# ANALOG_INPUT_CTRL.net
KiCad netlist of a schematic drawn in Altium Designer
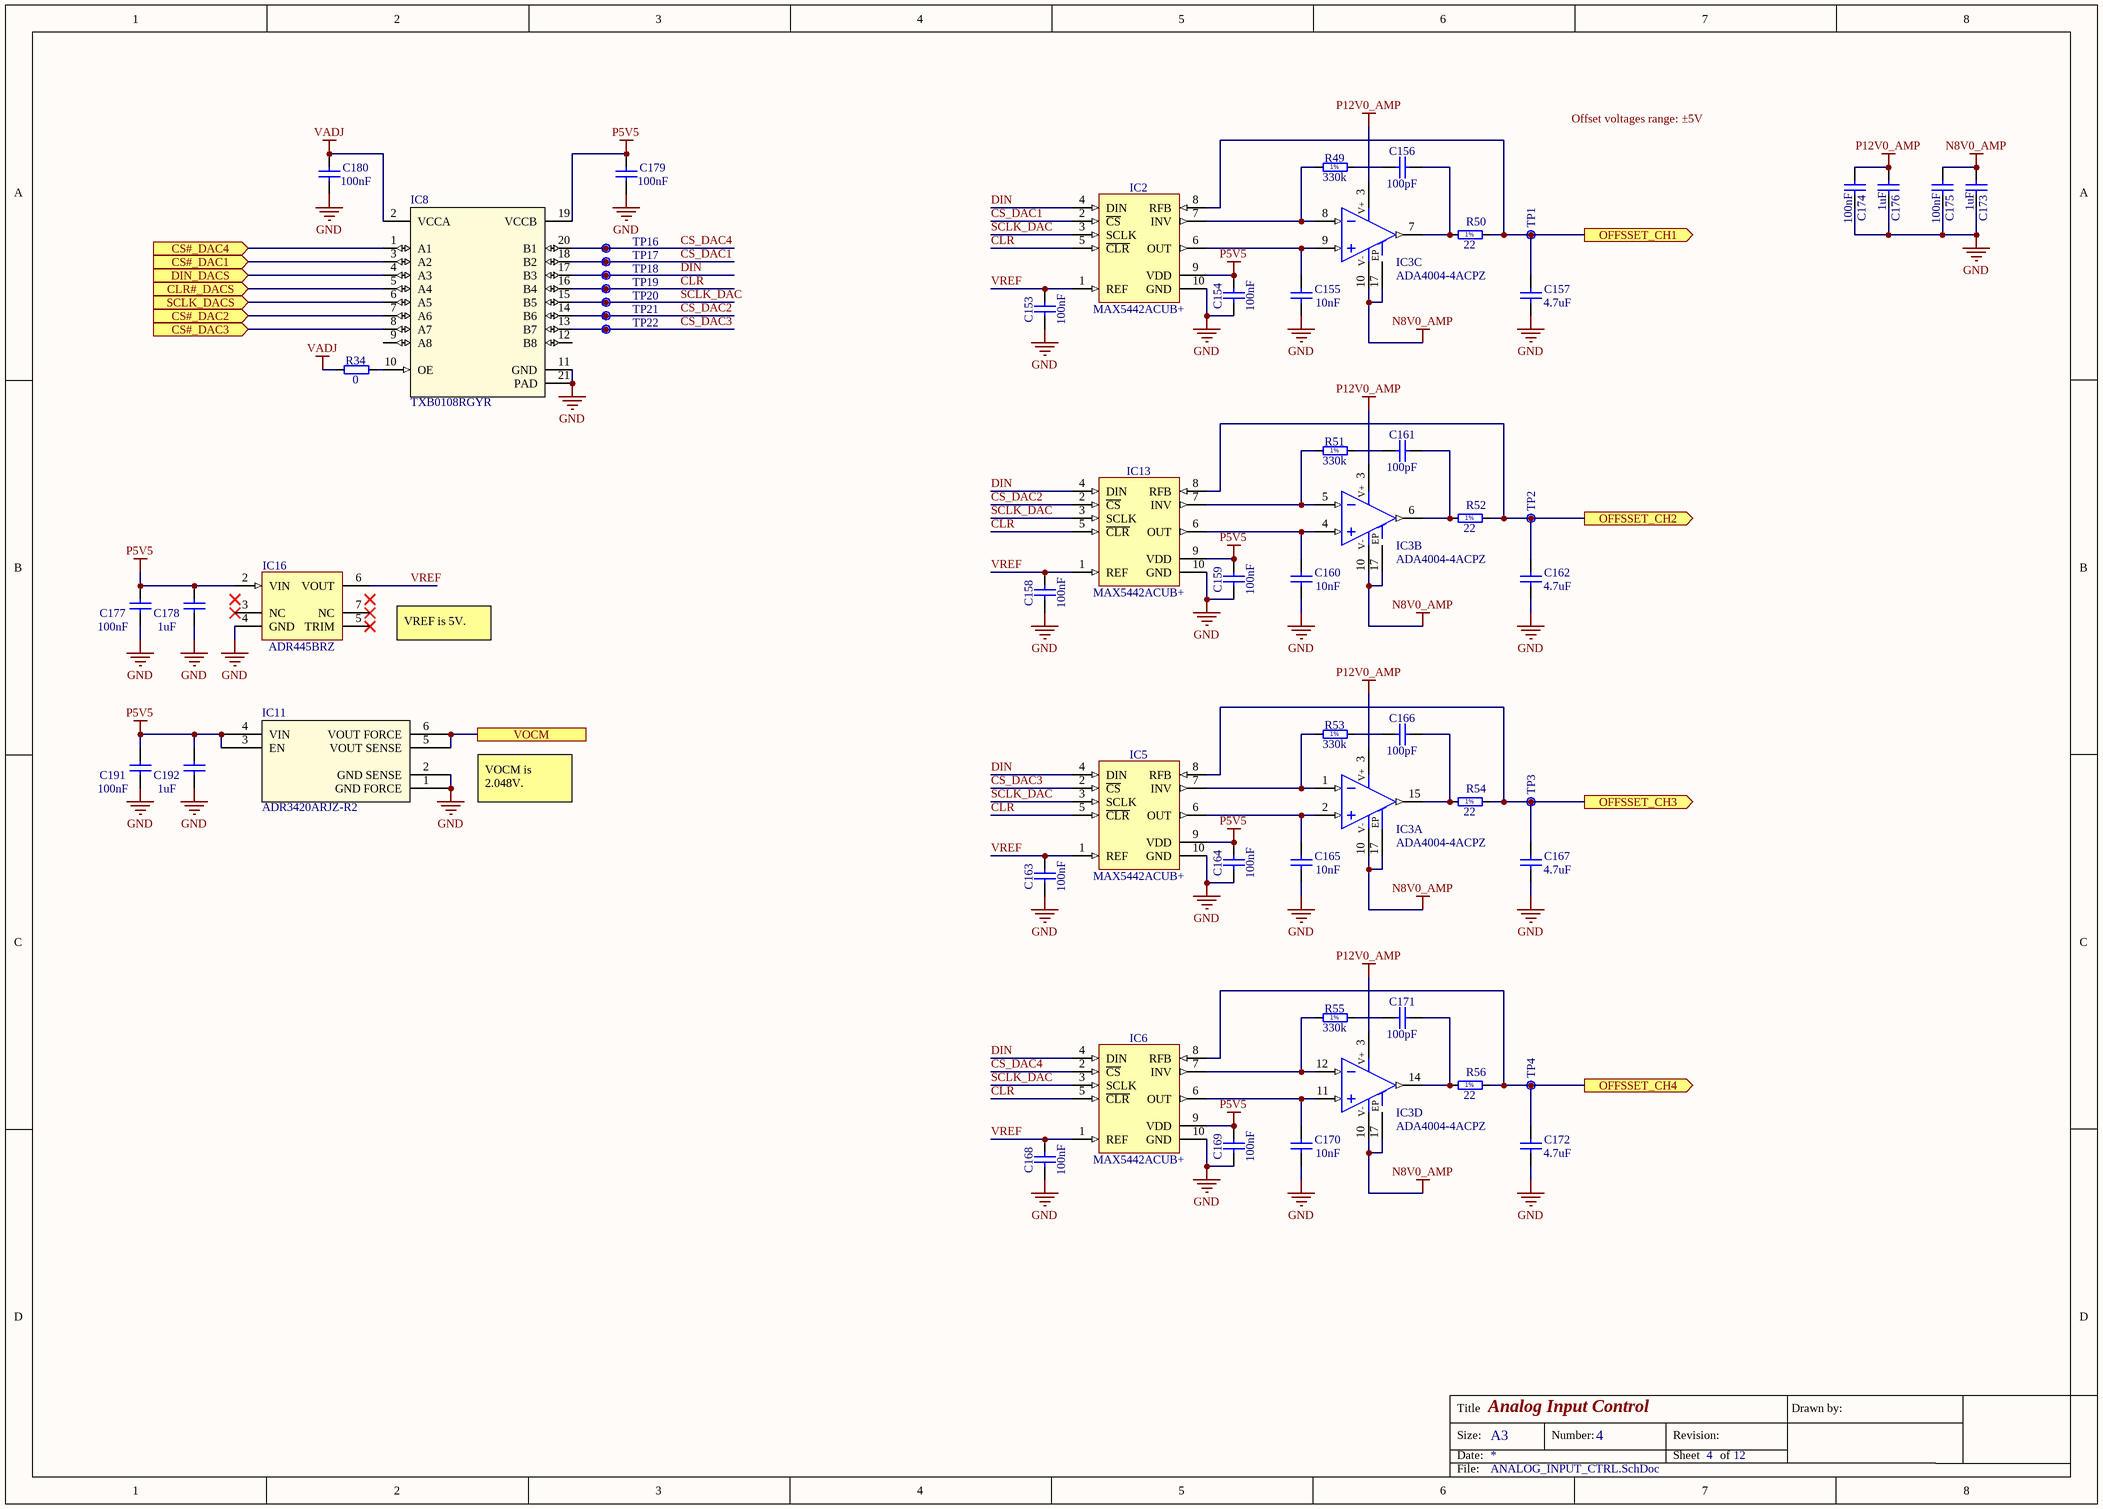
[diagram p0: ANALOG_INPUT_CTRL.SchDoc]

(export (version "E")
  (design (tool "Eeschema 10.0.6"))
  (components
    (comp (ref "C153")
      (value "100nF")
      (footprint "CAPC1005X55N")
      (description "Non-polarised capacitor")
      (fields
        (field (name "PART NUMBER") "CC0402_100NF_16V_10%_X7R")
        (field (name "VOLTAGE") "16V")
        (field (name "AUTHOR") "CERN DEM JLC")
      )
      (libsource (lib "Capacitors") (part "Capacitor - non polarized"))
    )
    (comp (ref "C154")
      (value "100nF")
      (footprint "CAPC1005X55N")
      (description "Non-polarised capacitor")
      (fields
        (field (name "PART NUMBER") "CC0402_100NF_16V_10%_X7R")
        (field (name "VOLTAGE") "16V")
        (field (name "AUTHOR") "CERN DEM JLC")
      )
      (libsource (lib "Capacitors") (part "Capacitor - non polarized"))
    )
    (comp (ref "C155")
      (value "10nF")
      (footprint "CAPC1608X87N")
      (description "Non-polarised capacitor")
      (fields
        (field (name "MANUFACTURER1 PART NUMBER") "223858615636")
        (field (name "MANUFACTURER") "GENERIC")
        (field (name "AUTHOR") "CERN DEM JLC")
      )
      (libsource (lib "Capacitors") (part "Capacitor - non polarized"))
    )
    (comp (ref "C156")
      (value "100pF")
      (footprint "CAPC1608X87N")
      (description "Non-polarised capacitor")
      (fields
        (field (name "PART NUMBER") "CC0603_100PF_50V_5%_NP0")
        (field (name "VOLTAGE") "50V")
        (field (name "AUTHOR") "CERN DEM JLC")
      )
      (libsource (lib "Capacitors") (part "Capacitor - non polarized"))
    )
    (comp (ref "C157")
      (value "4.7uF")
      (footprint "CAPC2012X135N")
      (description "Non-polarised capacitor")
      (fields
        (field (name "PART NUMBER") "CC0805_4.7UF_16V_10%_X7R")
        (field (name "VOLTAGE") "16V")
        (field (name "AUTHOR") "CERN DEM JLC")
      )
      (libsource (lib "Capacitors") (part "Capacitor - non polarized"))
    )
    (comp (ref "C158")
      (value "100nF")
      (footprint "CAPC1005X55N")
      (description "Non-polarised capacitor")
      (fields
        (field (name "PART NUMBER") "CC0402_100NF_16V_10%_X7R")
        (field (name "VOLTAGE") "16V")
        (field (name "AUTHOR") "CERN DEM JLC")
      )
      (libsource (lib "Capacitors") (part "Capacitor - non polarized"))
    )
    (comp (ref "C159")
      (value "100nF")
      (footprint "CAPC1005X55N")
      (description "Non-polarised capacitor")
      (fields
        (field (name "PART NUMBER") "CC0402_100NF_16V_10%_X7R")
        (field (name "VOLTAGE") "16V")
        (field (name "AUTHOR") "CERN DEM JLC")
      )
      (libsource (lib "Capacitors") (part "Capacitor - non polarized"))
    )
    (comp (ref "C160")
      (value "10nF")
      (footprint "CAPC1608X87N")
      (description "Non-polarised capacitor")
      (fields
        (field (name "MANUFACTURER1 PART NUMBER") "223858615636")
        (field (name "MANUFACTURER") "GENERIC")
        (field (name "AUTHOR") "CERN DEM JLC")
      )
      (libsource (lib "Capacitors") (part "Capacitor - non polarized"))
    )
    (comp (ref "C161")
      (value "100pF")
      (footprint "CAPC1608X87N")
      (description "Non-polarised capacitor")
      (fields
        (field (name "PART NUMBER") "CC0603_100PF_50V_5%_NP0")
        (field (name "VOLTAGE") "50V")
        (field (name "AUTHOR") "CERN DEM JLC")
      )
      (libsource (lib "Capacitors") (part "Capacitor - non polarized"))
    )
    (comp (ref "C162")
      (value "4.7uF")
      (footprint "CAPC2012X135N")
      (description "Non-polarised capacitor")
      (fields
        (field (name "PART NUMBER") "CC0805_4.7UF_16V_10%_X7R")
        (field (name "VOLTAGE") "16V")
        (field (name "AUTHOR") "CERN DEM JLC")
      )
      (libsource (lib "Capacitors") (part "Capacitor - non polarized"))
    )
    (comp (ref "C163")
      (value "100nF")
      (footprint "CAPC1005X55N")
      (description "Non-polarised capacitor")
      (fields
        (field (name "PART NUMBER") "CC0402_100NF_16V_10%_X7R")
        (field (name "VOLTAGE") "16V")
        (field (name "AUTHOR") "CERN DEM JLC")
      )
      (libsource (lib "Capacitors") (part "Capacitor - non polarized"))
    )
    (comp (ref "C164")
      (value "100nF")
      (footprint "CAPC1005X55N")
      (description "Non-polarised capacitor")
      (fields
        (field (name "PART NUMBER") "CC0402_100NF_16V_10%_X7R")
        (field (name "VOLTAGE") "16V")
        (field (name "AUTHOR") "CERN DEM JLC")
      )
      (libsource (lib "Capacitors") (part "Capacitor - non polarized"))
    )
    (comp (ref "C165")
      (value "10nF")
      (footprint "CAPC1608X87N")
      (description "Non-polarised capacitor")
      (fields
        (field (name "MANUFACTURER1 PART NUMBER") "223858615636")
        (field (name "MANUFACTURER") "GENERIC")
        (field (name "AUTHOR") "CERN DEM JLC")
      )
      (libsource (lib "Capacitors") (part "Capacitor - non polarized"))
    )
    (comp (ref "C166")
      (value "100pF")
      (footprint "CAPC1608X87N")
      (description "Non-polarised capacitor")
      (fields
        (field (name "PART NUMBER") "CC0603_100PF_50V_5%_NP0")
        (field (name "VOLTAGE") "50V")
        (field (name "AUTHOR") "CERN DEM JLC")
      )
      (libsource (lib "Capacitors") (part "Capacitor - non polarized"))
    )
    (comp (ref "C167")
      (value "4.7uF")
      (footprint "CAPC2012X135N")
      (description "Non-polarised capacitor")
      (fields
        (field (name "PART NUMBER") "CC0805_4.7UF_16V_10%_X7R")
        (field (name "VOLTAGE") "16V")
        (field (name "AUTHOR") "CERN DEM JLC")
      )
      (libsource (lib "Capacitors") (part "Capacitor - non polarized"))
    )
    (comp (ref "C168")
      (value "100nF")
      (footprint "CAPC1005X55N")
      (description "Non-polarised capacitor")
      (fields
        (field (name "PART NUMBER") "CC0402_100NF_16V_10%_X7R")
        (field (name "VOLTAGE") "16V")
        (field (name "AUTHOR") "CERN DEM JLC")
      )
      (libsource (lib "Capacitors") (part "Capacitor - non polarized"))
    )
    (comp (ref "C169")
      (value "100nF")
      (footprint "CAPC1005X55N")
      (description "Non-polarised capacitor")
      (fields
        (field (name "PART NUMBER") "CC0402_100NF_16V_10%_X7R")
        (field (name "VOLTAGE") "16V")
        (field (name "AUTHOR") "CERN DEM JLC")
      )
      (libsource (lib "Capacitors") (part "Capacitor - non polarized"))
    )
    (comp (ref "C170")
      (value "10nF")
      (footprint "CAPC1608X87N")
      (description "Non-polarised capacitor")
      (fields
        (field (name "MANUFACTURER1 PART NUMBER") "223858615636")
        (field (name "MANUFACTURER") "GENERIC")
        (field (name "AUTHOR") "CERN DEM JLC")
      )
      (libsource (lib "Capacitors") (part "Capacitor - non polarized"))
    )
    (comp (ref "C171")
      (value "100pF")
      (footprint "CAPC1608X87N")
      (description "Non-polarised capacitor")
      (fields
        (field (name "PART NUMBER") "CC0603_100PF_50V_5%_NP0")
        (field (name "VOLTAGE") "50V")
        (field (name "AUTHOR") "CERN DEM JLC")
      )
      (libsource (lib "Capacitors") (part "Capacitor - non polarized"))
    )
    (comp (ref "C172")
      (value "4.7uF")
      (footprint "CAPC2012X135N")
      (description "Non-polarised capacitor")
      (fields
        (field (name "PART NUMBER") "CC0805_4.7UF_16V_10%_X7R")
        (field (name "VOLTAGE") "16V")
        (field (name "AUTHOR") "CERN DEM JLC")
      )
      (libsource (lib "Capacitors") (part "Capacitor - non polarized"))
    )
    (comp (ref "C173")
      (value "1uF")
      (footprint "CAPC1608X87N")
      (description "Non-polarised capacitor")
      (fields
        (field (name "MANUFACTURER") "GENERIC")
        (field (name "PART NUMBER") "CC0603_1UF_16V_10%_X7R")
        (field (name "AUTHOR") "CERN DEM JLC")
      )
      (libsource (lib "Capacitors") (part "Capacitor - non polarized"))
    )
    (comp (ref "C174")
      (value "100nF")
      (footprint "CAPC1608X87N")
      (description "Non-polarised capacitor")
      (fields
        (field (name "MANUFACTURER") "GENERIC")
        (field (name "PART NUMBER") "CC0603_100NF_50V_10%_X7R")
        (field (name "AUTHOR") "CERN DEM JLC")
      )
      (libsource (lib "Capacitors") (part "Capacitor - non polarized"))
    )
    (comp (ref "C175")
      (value "100nF")
      (footprint "CAPC1608X87N")
      (description "Non-polarised capacitor")
      (fields
        (field (name "MANUFACTURER") "GENERIC")
        (field (name "PART NUMBER") "CC0603_100NF_50V_10%_X7R")
        (field (name "AUTHOR") "CERN DEM JLC")
      )
      (libsource (lib "Capacitors") (part "Capacitor - non polarized"))
    )
    (comp (ref "C176")
      (value "1uF")
      (footprint "CAPC1608X87N")
      (description "Non-polarised capacitor")
      (fields
        (field (name "MANUFACTURER") "GENERIC")
        (field (name "PART NUMBER") "CC0603_1UF_16V_10%_X7R")
        (field (name "AUTHOR") "CERN DEM JLC")
      )
      (libsource (lib "Capacitors") (part "Capacitor - non polarized"))
    )
    (comp (ref "C177")
      (value "100nF")
      (footprint "CAPC1005X55N")
      (description "Non-polarised capacitor")
      (fields
        (field (name "PART NUMBER") "CC0402_100NF_16V_10%_X7R")
        (field (name "VOLTAGE") "16V")
        (field (name "AUTHOR") "CERN DEM JLC")
      )
      (libsource (lib "Capacitors") (part "Capacitor - non polarized"))
    )
    (comp (ref "C178")
      (value "1uF")
      (footprint "CAPC1608X87N")
      (description "Non-polarised capacitor")
      (fields
        (field (name "MANUFACTURER1 PART NUMBER") "223878615663")
        (field (name "MANUFACTURER") "GENERIC")
        (field (name "AUTHOR") "CERN DEM JLC")
      )
      (libsource (lib "Capacitors") (part "Capacitor - non polarized"))
    )
    (comp (ref "C179")
      (value "100nF")
      (footprint "CAPC0603X33N")
      (description "Non-polarised capacitor")
      (fields
        (field (name "TOLERANCE") "±10%")
        (field (name "PART NUMBER") "CC0201_100NF_6.3V_10%_X5R")
        (field (name "AUTHOR") "CERN DEM JLC")
      )
      (libsource (lib "Capacitors") (part "Capacitor - non polarized"))
    )
    (comp (ref "C180")
      (value "100nF")
      (footprint "CAPC0603X33N")
      (description "Non-polarised capacitor")
      (fields
        (field (name "TOLERANCE") "±10%")
        (field (name "PART NUMBER") "CC0201_100NF_6.3V_10%_X5R")
        (field (name "AUTHOR") "CERN DEM JLC")
      )
      (libsource (lib "Capacitors") (part "Capacitor - non polarized"))
    )
    (comp (ref "C191")
      (value "100nF")
      (footprint "CAPC1005X55N")
      (description "Non-polarised capacitor")
      (fields
        (field (name "PART NUMBER") "CC0402_100NF_16V_10%_X7R")
        (field (name "VOLTAGE") "16V")
        (field (name "AUTHOR") "CERN DEM JLC")
      )
      (libsource (lib "Capacitors") (part "Capacitor - non polarized"))
    )
    (comp (ref "C192")
      (value "1uF")
      (footprint "CAPC1608X87N")
      (description "Non-polarised capacitor")
      (fields
        (field (name "MANUFACTURER1 PART NUMBER") "223878615663")
        (field (name "MANUFACTURER") "GENERIC")
        (field (name "AUTHOR") "CERN DEM JLC")
      )
      (libsource (lib "Capacitors") (part "Capacitor - non polarized"))
    )
    (comp (ref "IC2")
      (value "MAX5442ACUB+")
      (footprint "SOP50P490X110-10N")
      (description "+5V, Serial-Input, Voltage-Output, 16-Bit ±2LSB DAC")
      (fields (field (name "MANUFACTURER") "MAXIM") (field (name "AUTHOR") "CERN DEM JLC"))
      (libsource (lib "ICs And Semiconductors") (part "MAX5442ACUB+"))
    )
    (comp (ref "IC3")
      (value "ADA4004-4ACPZ")
      (footprint "QFN65P400X400X100-17N-S225")
      (description "Quad Operational Amplifier")
      (fields (field (name "MANUFACTURER") "ANALOG DEVICES") (field (name "AUTHOR") "CERN DEM JLC"))
      (libsource (lib "ICs And Semiconductors") (part "ADA4004-4ACPZ"))
    )
    (comp (ref "IC5")
      (value "MAX5442ACUB+")
      (footprint "SOP50P490X110-10N")
      (description "+5V, Serial-Input, Voltage-Output, 16-Bit ±2LSB DAC")
      (fields (field (name "MANUFACTURER") "MAXIM") (field (name "AUTHOR") "CERN DEM JLC"))
      (libsource (lib "ICs And Semiconductors") (part "MAX5442ACUB+"))
    )
    (comp (ref "IC6")
      (value "MAX5442ACUB+")
      (footprint "SOP50P490X110-10N")
      (description "+5V, Serial-Input, Voltage-Output, 16-Bit ±2LSB DAC")
      (fields (field (name "MANUFACTURER") "MAXIM") (field (name "AUTHOR") "CERN DEM JLC"))
      (libsource (lib "ICs And Semiconductors") (part "MAX5442ACUB+"))
    )
    (comp (ref "IC8")
      (value "TXB0108RGYR")
      (footprint "RGY20_3P05x2P05")
      (description "8-Bit Bidirectional Voltage-Level Translator with Auto-Direction Sensing")
      (fields (field (name "MANUFACTURER") "Texas Instruments"))
      (libsource (lib "FMC_ADC") (part "TXB0108RGYR"))
    )
    (comp (ref "IC11")
      (value "ADR3420ARJZ-R2")
      (footprint "RJ_6")
      (description "Micropower, High Accuracy Voltage References - 2.048V")
      (fields (field (name "MANUFACTURER") "Analog Devices"))
      (libsource (lib "FMC_ADC") (part "ADR3420ARJZ-R2"))
    )
    (comp (ref "IC13")
      (value "MAX5442ACUB+")
      (footprint "SOP50P490X110-10N")
      (description "+5V, Serial-Input, Voltage-Output, 16-Bit ±2LSB DAC")
      (fields (field (name "MANUFACTURER") "MAXIM") (field (name "AUTHOR") "CERN DEM JLC"))
      (libsource (lib "ICs And Semiconductors") (part "MAX5442ACUB+"))
    )
    (comp (ref "IC16")
      (value "ADR445BRZ")
      (footprint "SOIC127P600X175-8N")
      (description "5V Ultralow Noise, LDO XFET Voltage References with Current Sink and Source")
      (fields (field (name "MANUFACTURER") "ANALOG DEVICES") (field (name "AUTHOR") "CERN DEM JLC"))
      (libsource (lib "ICs And Semiconductors") (part "ADR44x"))
    )
    (comp (ref "R34")
      (value "0")
      (footprint "RESC1005X40N")
      (description "Resistor")
      (fields
        (field (name "PART NUMBER") "R0402_0R_JUMPER")
        (field (name "MANUFACTURER") "GENERIC")
        (field (name "AUTHOR") "CERN DEM JLC")
      )
      (libsource (lib "Resistors") (part "Resistor"))
    )
    (comp (ref "R49")
      (value "330k")
      (footprint "RESC1608X55N")
      (description "Resistor - 1%")
      (fields
        (field (name "PART NUMBER") "R0603_330K_1%_0.1W_100PPM")
        (field (name "POWER") "0.1W")
        (field (name "AUTHOR") "CERN DEM JLC")
      )
      (libsource (lib "Resistors") (part "Resistor - 1%"))
    )
    (comp (ref "R50")
      (value "22")
      (footprint "RESC1608X55N")
      (description "Resistor - 1%")
      (fields
        (field (name "MANUFACTURER1 PART NUMBER") "NRC06F22R0TRF")
        (field (name "MANUFACTURER") "GENERIC")
        (field (name "AUTHOR") "CERN DEM JLC")
      )
      (libsource (lib "Resistors") (part "Resistor - 1%"))
    )
    (comp (ref "R51")
      (value "330k")
      (footprint "RESC1608X55N")
      (description "Resistor - 1%")
      (fields
        (field (name "PART NUMBER") "R0603_330K_1%_0.1W_100PPM")
        (field (name "POWER") "0.1W")
        (field (name "AUTHOR") "CERN DEM JLC")
      )
      (libsource (lib "Resistors") (part "Resistor - 1%"))
    )
    (comp (ref "R52")
      (value "22")
      (footprint "RESC1608X55N")
      (description "Resistor - 1%")
      (fields
        (field (name "MANUFACTURER1 PART NUMBER") "NRC06F22R0TRF")
        (field (name "MANUFACTURER") "GENERIC")
        (field (name "AUTHOR") "CERN DEM JLC")
      )
      (libsource (lib "Resistors") (part "Resistor - 1%"))
    )
    (comp (ref "R53")
      (value "330k")
      (footprint "RESC1608X55N")
      (description "Resistor - 1%")
      (fields
        (field (name "PART NUMBER") "R0603_330K_1%_0.1W_100PPM")
        (field (name "POWER") "0.1W")
        (field (name "AUTHOR") "CERN DEM JLC")
      )
      (libsource (lib "Resistors") (part "Resistor - 1%"))
    )
    (comp (ref "R54")
      (value "22")
      (footprint "RESC1608X55N")
      (description "Resistor - 1%")
      (fields
        (field (name "MANUFACTURER1 PART NUMBER") "NRC06F22R0TRF")
        (field (name "MANUFACTURER") "GENERIC")
        (field (name "AUTHOR") "CERN DEM JLC")
      )
      (libsource (lib "Resistors") (part "Resistor - 1%"))
    )
    (comp (ref "R55")
      (value "330k")
      (footprint "RESC1608X55N")
      (description "Resistor - 1%")
      (fields
        (field (name "PART NUMBER") "R0603_330K_1%_0.1W_100PPM")
        (field (name "POWER") "0.1W")
        (field (name "AUTHOR") "CERN DEM JLC")
      )
      (libsource (lib "Resistors") (part "Resistor - 1%"))
    )
    (comp (ref "R56")
      (value "22")
      (footprint "RESC1608X55N")
      (description "Resistor - 1%")
      (fields
        (field (name "MANUFACTURER1 PART NUMBER") "NRC06F22R0TRF")
        (field (name "MANUFACTURER") "GENERIC")
        (field (name "AUTHOR") "CERN DEM JLC")
      )
      (libsource (lib "Resistors") (part "Resistor - 1%"))
    )
    (comp (ref "TP1")
      (value "~")
      (footprint "TPS127")
      (description "Test Point")
      (fields (field (name "PART NUMBER") "SMD_PAD_1.27X1.27MM") (field (name "AUTHOR") "CERN DEM JLC"))
      (libsource (lib "Eletro-mechanical") (part "Test Point"))
    )
    (comp (ref "TP2")
      (value "~")
      (footprint "TPS127")
      (description "Test Point")
      (fields (field (name "PART NUMBER") "SMD_PAD_1.27X1.27MM") (field (name "AUTHOR") "CERN DEM JLC"))
      (libsource (lib "Eletro-mechanical") (part "Test Point"))
    )
    (comp (ref "TP3")
      (value "~")
      (footprint "TPS127")
      (description "Test Point")
      (fields (field (name "PART NUMBER") "SMD_PAD_1.27X1.27MM") (field (name "AUTHOR") "CERN DEM JLC"))
      (libsource (lib "Eletro-mechanical") (part "Test Point"))
    )
    (comp (ref "TP4")
      (value "~")
      (footprint "TPS127")
      (description "Test Point")
      (fields (field (name "PART NUMBER") "SMD_PAD_1.27X1.27MM") (field (name "AUTHOR") "CERN DEM JLC"))
      (libsource (lib "Eletro-mechanical") (part "Test Point"))
    )
    (comp (ref "TP16")
      (value "Test Point")
      (footprint "TPS62")
      (fields (field (name "PART NUMBER") "SMD_PAD_0.62X0.62MM") (field (name "AUTHOR") "CERN DEM JLC"))
      (libsource (lib "FMC_ADC") (part "Test Point"))
    )
    (comp (ref "TP17")
      (value "Test Point")
      (footprint "TPS62")
      (fields (field (name "PART NUMBER") "SMD_PAD_0.62X0.62MM") (field (name "AUTHOR") "CERN DEM JLC"))
      (libsource (lib "FMC_ADC") (part "Test Point"))
    )
    (comp (ref "TP18")
      (value "Test Point")
      (footprint "TPS62")
      (fields (field (name "PART NUMBER") "SMD_PAD_0.62X0.62MM") (field (name "AUTHOR") "CERN DEM JLC"))
      (libsource (lib "FMC_ADC") (part "Test Point"))
    )
    (comp (ref "TP19")
      (value "Test Point")
      (footprint "TPS62")
      (fields (field (name "PART NUMBER") "SMD_PAD_0.62X0.62MM") (field (name "AUTHOR") "CERN DEM JLC"))
      (libsource (lib "FMC_ADC") (part "Test Point"))
    )
    (comp (ref "TP20")
      (value "Test Point")
      (footprint "TPS62")
      (fields (field (name "PART NUMBER") "SMD_PAD_0.62X0.62MM") (field (name "AUTHOR") "CERN DEM JLC"))
      (libsource (lib "FMC_ADC") (part "Test Point"))
    )
    (comp (ref "TP21")
      (value "Test Point")
      (footprint "TPS62")
      (fields (field (name "PART NUMBER") "SMD_PAD_0.62X0.62MM") (field (name "AUTHOR") "CERN DEM JLC"))
      (libsource (lib "FMC_ADC") (part "Test Point"))
    )
    (comp (ref "TP22")
      (value "Test Point")
      (footprint "TPS62")
      (fields (field (name "PART NUMBER") "SMD_PAD_0.62X0.62MM") (field (name "AUTHOR") "CERN DEM JLC"))
      (libsource (lib "FMC_ADC") (part "Test Point"))
    )
  )
  (nets
    (net (code "1") (name "/CLR") (class "Default")
      (node (ref "IC13") (pin "5") (pinfunction "~{CLR}_5") (pintype "input"))
      (node (ref "IC2") (pin "5") (pinfunction "~{CLR}_5") (pintype "input"))
      (node (ref "IC5") (pin "5") (pinfunction "~{CLR}_5") (pintype "input"))
      (node (ref "IC6") (pin "5") (pinfunction "~{CLR}_5") (pintype "input"))
      (node (ref "IC8") (pin "16") (pinfunction "B4_16") (pintype "bidirectional"))
      (node (ref "TP19") (pin "1") (pinfunction "1_1") (pintype "bidirectional"))
    )
    (net (code "2") (name "/CLR#_DACS") (class "Default")
      (node (ref "IC8") (pin "5") (pinfunction "A4_5") (pintype "bidirectional"))
    )
    (net (code "3") (name "/CS#_DAC1") (class "Default")
      (node (ref "IC8") (pin "3") (pinfunction "A2_3") (pintype "bidirectional"))
    )
    (net (code "4") (name "/CS#_DAC2") (class "Default")
      (node (ref "IC8") (pin "7") (pinfunction "A6_7") (pintype "bidirectional"))
    )
    (net (code "5") (name "/CS#_DAC3") (class "Default")
      (node (ref "IC8") (pin "8") (pinfunction "A7_8") (pintype "bidirectional"))
    )
    (net (code "6") (name "/CS#_DAC4") (class "Default")
      (node (ref "IC8") (pin "1") (pinfunction "A1_1") (pintype "bidirectional"))
    )
    (net (code "7") (name "/CS_DAC1") (class "Default")
      (node (ref "IC2") (pin "2") (pinfunction "~{CS}_2") (pintype "input"))
      (node (ref "IC8") (pin "18") (pinfunction "B2_18") (pintype "bidirectional"))
      (node (ref "TP17") (pin "1") (pinfunction "1_1") (pintype "bidirectional"))
    )
    (net (code "8") (name "/CS_DAC2") (class "Default")
      (node (ref "IC13") (pin "2") (pinfunction "~{CS}_2") (pintype "input"))
      (node (ref "IC8") (pin "14") (pinfunction "B6_14") (pintype "bidirectional"))
      (node (ref "TP21") (pin "1") (pinfunction "1_1") (pintype "bidirectional"))
    )
    (net (code "9") (name "/CS_DAC3") (class "Default")
      (node (ref "IC5") (pin "2") (pinfunction "~{CS}_2") (pintype "input"))
      (node (ref "IC8") (pin "13") (pinfunction "B7_13") (pintype "bidirectional"))
      (node (ref "TP22") (pin "1") (pinfunction "1_1") (pintype "bidirectional"))
    )
    (net (code "10") (name "/CS_DAC4") (class "Default")
      (node (ref "IC6") (pin "2") (pinfunction "~{CS}_2") (pintype "input"))
      (node (ref "IC8") (pin "20") (pinfunction "B1_20") (pintype "bidirectional"))
      (node (ref "TP16") (pin "1") (pinfunction "1_1") (pintype "bidirectional"))
    )
    (net (code "11") (name "/DIN") (class "Default")
      (node (ref "IC13") (pin "4") (pinfunction "DIN_4") (pintype "input"))
      (node (ref "IC2") (pin "4") (pinfunction "DIN_4") (pintype "input"))
      (node (ref "IC5") (pin "4") (pinfunction "DIN_4") (pintype "input"))
      (node (ref "IC6") (pin "4") (pinfunction "DIN_4") (pintype "input"))
      (node (ref "IC8") (pin "17") (pinfunction "B3_17") (pintype "bidirectional"))
      (node (ref "TP18") (pin "1") (pinfunction "1_1") (pintype "bidirectional"))
    )
    (net (code "12") (name "/DIN_DACS") (class "Default")
      (node (ref "IC8") (pin "4") (pinfunction "A3_4") (pintype "bidirectional"))
    )
    (net (code "13") (name "/OFFSSET_CH1") (class "Default")
      (node (ref "C157") (pin "1") (pinfunction "1_1") (pintype "passive"))
      (node (ref "IC2") (pin "8") (pinfunction "RFB_8") (pintype "input"))
      (node (ref "R50") (pin "2") (pinfunction "2_2") (pintype "passive"))
      (node (ref "TP1") (pin "1") (pinfunction "1_1") (pintype "bidirectional"))
    )
    (net (code "14") (name "/OFFSSET_CH2") (class "Default")
      (node (ref "C162") (pin "1") (pinfunction "1_1") (pintype "passive"))
      (node (ref "IC13") (pin "8") (pinfunction "RFB_8") (pintype "input"))
      (node (ref "R52") (pin "2") (pinfunction "2_2") (pintype "passive"))
      (node (ref "TP2") (pin "1") (pinfunction "1_1") (pintype "bidirectional"))
    )
    (net (code "15") (name "/OFFSSET_CH3") (class "Default")
      (node (ref "C167") (pin "1") (pinfunction "1_1") (pintype "passive"))
      (node (ref "IC5") (pin "8") (pinfunction "RFB_8") (pintype "input"))
      (node (ref "R54") (pin "2") (pinfunction "2_2") (pintype "passive"))
      (node (ref "TP3") (pin "1") (pinfunction "1_1") (pintype "bidirectional"))
    )
    (net (code "16") (name "/OFFSSET_CH4") (class "Default")
      (node (ref "C172") (pin "1") (pinfunction "1_1") (pintype "passive"))
      (node (ref "IC6") (pin "8") (pinfunction "RFB_8") (pintype "input"))
      (node (ref "R56") (pin "2") (pinfunction "2_2") (pintype "passive"))
      (node (ref "TP4") (pin "1") (pinfunction "1_1") (pintype "bidirectional"))
    )
    (net (code "17") (name "/SCLK_DAC") (class "Default")
      (node (ref "IC13") (pin "3") (pinfunction "SCLK_3") (pintype "input"))
      (node (ref "IC2") (pin "3") (pinfunction "SCLK_3") (pintype "input"))
      (node (ref "IC5") (pin "3") (pinfunction "SCLK_3") (pintype "input"))
      (node (ref "IC6") (pin "3") (pinfunction "SCLK_3") (pintype "input"))
      (node (ref "IC8") (pin "15") (pinfunction "B5_15") (pintype "bidirectional"))
      (node (ref "TP20") (pin "1") (pinfunction "1_1") (pintype "bidirectional"))
    )
    (net (code "18") (name "/SCLK_DACS") (class "Default")
      (node (ref "IC8") (pin "6") (pinfunction "A5_6") (pintype "bidirectional"))
    )
    (net (code "19") (name "/VOCM") (class "Default")
      (node (ref "IC11") (pin "5") (pinfunction "VOUT_SENSE_5") (pintype "passive"))
      (node (ref "IC11") (pin "6") (pinfunction "VOUT_FORCE_6") (pintype "passive"))
    )
    (net (code "20") (name "/VREF") (class "Default")
      (node (ref "C153") (pin "2") (pinfunction "2_2") (pintype "passive"))
      (node (ref "C158") (pin "2") (pinfunction "2_2") (pintype "passive"))
      (node (ref "C163") (pin "2") (pinfunction "2_2") (pintype "passive"))
      (node (ref "C168") (pin "2") (pinfunction "2_2") (pintype "passive"))
      (node (ref "IC13") (pin "1") (pinfunction "REF_1") (pintype "input"))
      (node (ref "IC16") (pin "6") (pinfunction "VOUT_6") (pintype "power_in"))
      (node (ref "IC2") (pin "1") (pinfunction "REF_1") (pintype "input"))
      (node (ref "IC5") (pin "1") (pinfunction "REF_1") (pintype "input"))
      (node (ref "IC6") (pin "1") (pinfunction "REF_1") (pintype "input"))
    )
    (net (code "21") (name "GND") (class "Default")
      (node (ref "C153") (pin "1") (pinfunction "1_1") (pintype "passive"))
      (node (ref "C154") (pin "1") (pinfunction "1_1") (pintype "passive"))
      (node (ref "C155") (pin "1") (pinfunction "1_1") (pintype "passive"))
      (node (ref "C157") (pin "2") (pinfunction "2_2") (pintype "passive"))
      (node (ref "C158") (pin "1") (pinfunction "1_1") (pintype "passive"))
      (node (ref "C159") (pin "1") (pinfunction "1_1") (pintype "passive"))
      (node (ref "C160") (pin "1") (pinfunction "1_1") (pintype "passive"))
      (node (ref "C162") (pin "2") (pinfunction "2_2") (pintype "passive"))
      (node (ref "C163") (pin "1") (pinfunction "1_1") (pintype "passive"))
      (node (ref "C164") (pin "1") (pinfunction "1_1") (pintype "passive"))
      (node (ref "C165") (pin "1") (pinfunction "1_1") (pintype "passive"))
      (node (ref "C167") (pin "2") (pinfunction "2_2") (pintype "passive"))
      (node (ref "C168") (pin "1") (pinfunction "1_1") (pintype "passive"))
      (node (ref "C169") (pin "1") (pinfunction "1_1") (pintype "passive"))
      (node (ref "C170") (pin "1") (pinfunction "1_1") (pintype "passive"))
      (node (ref "C172") (pin "2") (pinfunction "2_2") (pintype "passive"))
      (node (ref "C173") (pin "2") (pinfunction "2_2") (pintype "passive"))
      (node (ref "C174") (pin "2") (pinfunction "2_2") (pintype "passive"))
      (node (ref "C175") (pin "2") (pinfunction "2_2") (pintype "passive"))
      (node (ref "C176") (pin "2") (pinfunction "2_2") (pintype "passive"))
      (node (ref "C177") (pin "1") (pinfunction "1_1") (pintype "passive"))
      (node (ref "C178") (pin "1") (pinfunction "1_1") (pintype "passive"))
      (node (ref "C179") (pin "1") (pinfunction "1_1") (pintype "passive"))
      (node (ref "C180") (pin "1") (pinfunction "1_1") (pintype "passive"))
      (node (ref "C191") (pin "1") (pinfunction "1_1") (pintype "passive"))
      (node (ref "C192") (pin "1") (pinfunction "1_1") (pintype "passive"))
      (node (ref "IC11") (pin "1") (pinfunction "GND_FORCE_1") (pintype "passive"))
      (node (ref "IC11") (pin "2") (pinfunction "GND_SENSE_2") (pintype "passive"))
      (node (ref "IC13") (pin "10") (pinfunction "GND_10") (pintype "power_in"))
      (node (ref "IC16") (pin "4") (pinfunction "GND_4") (pintype "power_in"))
      (node (ref "IC2") (pin "10") (pinfunction "GND_10") (pintype "power_in"))
      (node (ref "IC5") (pin "10") (pinfunction "GND_10") (pintype "power_in"))
      (node (ref "IC6") (pin "10") (pinfunction "GND_10") (pintype "power_in"))
      (node (ref "IC8") (pin "11") (pinfunction "GND_11") (pintype "power_in"))
      (node (ref "IC8") (pin "21") (pinfunction "PAD_21") (pintype "power_in"))
    )
    (net (code "22") (name "N8V0_AMP") (class "Default")
      (node (ref "C173") (pin "1") (pinfunction "1_1") (pintype "passive"))
      (node (ref "C175") (pin "1") (pinfunction "1_1") (pintype "passive"))
      (node (ref "IC3") (pin "10") (pinfunction "V-_10") (pintype "power_in"))
      (node (ref "IC3") (pin "17") (pinfunction "EP_17") (pintype "power_in"))
    )
    (net (code "23") (name "Net-(C156-Pad1)") (class "Default")
      (node (ref "C156") (pin "1") (pinfunction "1_1") (pintype "passive"))
      (node (ref "R49") (pin "2") (pinfunction "2_2") (pintype "passive"))
    )
    (net (code "24") (name "Net-(C161-Pad1)") (class "Default")
      (node (ref "C161") (pin "1") (pinfunction "1_1") (pintype "passive"))
      (node (ref "R51") (pin "2") (pinfunction "2_2") (pintype "passive"))
    )
    (net (code "25") (name "Net-(C166-Pad1)") (class "Default")
      (node (ref "C166") (pin "1") (pinfunction "1_1") (pintype "passive"))
      (node (ref "R53") (pin "2") (pinfunction "2_2") (pintype "passive"))
    )
    (net (code "26") (name "Net-(C171-Pad1)") (class "Default")
      (node (ref "C171") (pin "1") (pinfunction "1_1") (pintype "passive"))
      (node (ref "R55") (pin "2") (pinfunction "2_2") (pintype "passive"))
    )
    (net (code "27") (name "Net-(IC2-INV)") (class "Default")
      (node (ref "IC2") (pin "7") (pinfunction "INV_7") (pintype "output"))
      (node (ref "IC3") (pin "8") (pinfunction "IN-_8") (pintype "input"))
      (node (ref "R49") (pin "1") (pinfunction "1_1") (pintype "passive"))
    )
    (net (code "28") (name "Net-(IC2-OUT)") (class "Default")
      (node (ref "C155") (pin "2") (pinfunction "2_2") (pintype "passive"))
      (node (ref "IC2") (pin "6") (pinfunction "OUT_6") (pintype "output"))
      (node (ref "IC3") (pin "9") (pinfunction "IN+_9") (pintype "input"))
    )
    (net (code "29") (name "Net-(IC3A-IN+)") (class "Default")
      (node (ref "C165") (pin "2") (pinfunction "2_2") (pintype "passive"))
      (node (ref "IC3") (pin "2") (pinfunction "IN+_2") (pintype "input"))
      (node (ref "IC5") (pin "6") (pinfunction "OUT_6") (pintype "output"))
    )
    (net (code "30") (name "Net-(IC3A-IN-)") (class "Default")
      (node (ref "IC3") (pin "1") (pinfunction "IN-_1") (pintype "input"))
      (node (ref "IC5") (pin "7") (pinfunction "INV_7") (pintype "output"))
      (node (ref "R53") (pin "1") (pinfunction "1_1") (pintype "passive"))
    )
    (net (code "31") (name "Net-(IC3A-OUT)") (class "Default")
      (node (ref "C166") (pin "2") (pinfunction "2_2") (pintype "passive"))
      (node (ref "IC3") (pin "15") (pinfunction "OUT_15") (pintype "output"))
      (node (ref "R54") (pin "1") (pinfunction "1_1") (pintype "passive"))
    )
    (net (code "32") (name "Net-(IC3B-OUT)") (class "Default")
      (node (ref "C161") (pin "2") (pinfunction "2_2") (pintype "passive"))
      (node (ref "IC3") (pin "6") (pinfunction "OUT_6") (pintype "output"))
      (node (ref "R52") (pin "1") (pinfunction "1_1") (pintype "passive"))
    )
    (net (code "33") (name "Net-(IC3C-OUT)") (class "Default")
      (node (ref "C156") (pin "2") (pinfunction "2_2") (pintype "passive"))
      (node (ref "IC3") (pin "7") (pinfunction "OUT_7") (pintype "output"))
      (node (ref "R50") (pin "1") (pinfunction "1_1") (pintype "passive"))
    )
    (net (code "34") (name "Net-(IC3D-IN+)") (class "Default")
      (node (ref "C170") (pin "2") (pinfunction "2_2") (pintype "passive"))
      (node (ref "IC3") (pin "11") (pinfunction "IN+_11") (pintype "input"))
      (node (ref "IC6") (pin "6") (pinfunction "OUT_6") (pintype "output"))
    )
    (net (code "35") (name "Net-(IC3D-IN-)") (class "Default")
      (node (ref "IC3") (pin "12") (pinfunction "IN-_12") (pintype "input"))
      (node (ref "IC6") (pin "7") (pinfunction "INV_7") (pintype "output"))
      (node (ref "R55") (pin "1") (pinfunction "1_1") (pintype "passive"))
    )
    (net (code "36") (name "Net-(IC3D-OUT)") (class "Default")
      (node (ref "C171") (pin "2") (pinfunction "2_2") (pintype "passive"))
      (node (ref "IC3") (pin "14") (pinfunction "OUT_14") (pintype "output"))
      (node (ref "R56") (pin "1") (pinfunction "1_1") (pintype "passive"))
    )
    (net (code "37") (name "Net-(IC8-OE)") (class "Default")
      (node (ref "IC8") (pin "10") (pinfunction "OE_10") (pintype "input"))
      (node (ref "R34") (pin "2") (pinfunction "2_2") (pintype "passive"))
    )
    (net (code "38") (name "Net-(IC13-INV)") (class "Default")
      (node (ref "IC13") (pin "7") (pinfunction "INV_7") (pintype "output"))
      (node (ref "IC3") (pin "5") (pinfunction "IN-_5") (pintype "input"))
      (node (ref "R51") (pin "1") (pinfunction "1_1") (pintype "passive"))
    )
    (net (code "39") (name "Net-(IC13-OUT)") (class "Default")
      (node (ref "C160") (pin "2") (pinfunction "2_2") (pintype "passive"))
      (node (ref "IC13") (pin "6") (pinfunction "OUT_6") (pintype "output"))
      (node (ref "IC3") (pin "4") (pinfunction "IN+_4") (pintype "input"))
    )
    (net (code "40") (name "P5V5") (class "Default")
      (node (ref "C154") (pin "2") (pinfunction "2_2") (pintype "passive"))
      (node (ref "C159") (pin "2") (pinfunction "2_2") (pintype "passive"))
      (node (ref "C164") (pin "2") (pinfunction "2_2") (pintype "passive"))
      (node (ref "C169") (pin "2") (pinfunction "2_2") (pintype "passive"))
      (node (ref "C177") (pin "2") (pinfunction "2_2") (pintype "passive"))
      (node (ref "C178") (pin "2") (pinfunction "2_2") (pintype "passive"))
      (node (ref "C179") (pin "2") (pinfunction "2_2") (pintype "passive"))
      (node (ref "C191") (pin "2") (pinfunction "2_2") (pintype "passive"))
      (node (ref "C192") (pin "2") (pinfunction "2_2") (pintype "passive"))
      (node (ref "IC11") (pin "3") (pinfunction "EN_3") (pintype "passive"))
      (node (ref "IC11") (pin "4") (pinfunction "VIN_4") (pintype "passive"))
      (node (ref "IC13") (pin "9") (pinfunction "VDD_9") (pintype "power_in"))
      (node (ref "IC16") (pin "2") (pinfunction "VIN_2") (pintype "input"))
      (node (ref "IC2") (pin "9") (pinfunction "VDD_9") (pintype "power_in"))
      (node (ref "IC5") (pin "9") (pinfunction "VDD_9") (pintype "power_in"))
      (node (ref "IC6") (pin "9") (pinfunction "VDD_9") (pintype "power_in"))
      (node (ref "IC8") (pin "19") (pinfunction "VCCB_19") (pintype "power_in"))
    )
    (net (code "41") (name "P12V0_AMP") (class "Default")
      (node (ref "C174") (pin "1") (pinfunction "1_1") (pintype "passive"))
      (node (ref "C176") (pin "1") (pinfunction "1_1") (pintype "passive"))
      (node (ref "IC3") (pin "3") (pinfunction "V+_3") (pintype "power_in"))
    )
    (net (code "42") (name "VADJ") (class "Default")
      (node (ref "C180") (pin "2") (pinfunction "2_2") (pintype "passive"))
      (node (ref "IC8") (pin "2") (pinfunction "VCCA_2") (pintype "power_in"))
      (node (ref "R34") (pin "1") (pinfunction "1_1") (pintype "passive"))
    )
    (net (code "43") (name "unconnected-(IC8-A8-Pad9)") (class "Default")
      (node (ref "IC8") (pin "9") (pinfunction "A8_9") (pintype "bidirectional"))
    )
    (net (code "44") (name "unconnected-(IC8-B8-Pad12)") (class "Default")
      (node (ref "IC8") (pin "12") (pinfunction "B8_12") (pintype "bidirectional"))
    )
    (net (code "45") (name "unconnected-(IC16-NC-Pad3)") (class "Default")
      (node (ref "IC16") (pin "3") (pinfunction "NC_3") (pintype "passive+no_connect"))
    )
    (net (code "46") (name "unconnected-(IC16-NC-Pad7)") (class "Default")
      (node (ref "IC16") (pin "7") (pinfunction "NC_7") (pintype "passive+no_connect"))
    )
    (net (code "47") (name "unconnected-(IC16-TRIM-Pad5)") (class "Default")
      (node (ref "IC16") (pin "5") (pinfunction "TRIM_5") (pintype "passive+no_connect"))
    )
  )
)
